# N64A_FA_E7x.net
KiCad netlist of a schematic drawn in EAGLE
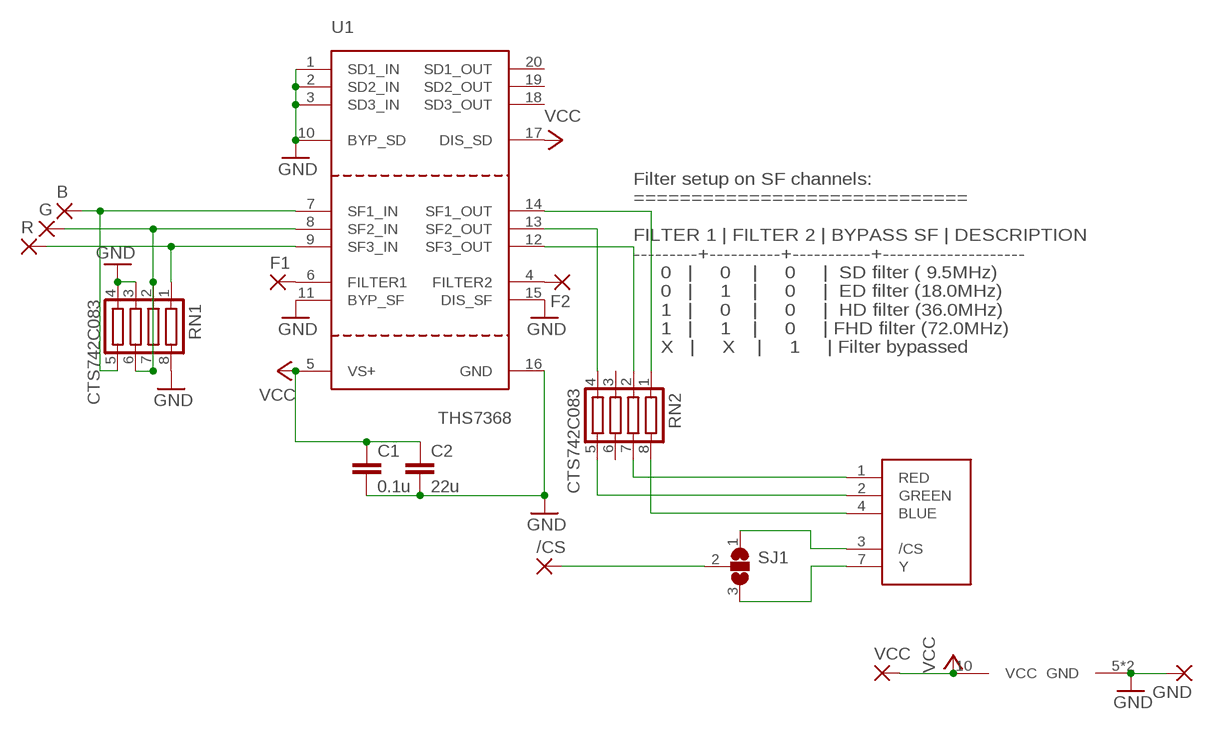
[diagram p0: schematic, sheet 1]

(export (version "E")
  (design (tool "Eeschema 10.0.6"))
  (components
    (comp (ref "/CS")
      (value "SMD2")
      (footprint "eagle-import:SMD1,27-2,54")
      (libsource (lib "eagle-import") (part "SMD2"))
    )
    (comp (ref "B")
      (value "SMD2")
      (footprint "eagle-import:SMD1,27-2,54")
      (libsource (lib "eagle-import") (part "SMD2"))
    )
    (comp (ref "C1")
      (value "0.1u")
      (footprint "eagle-import:C0603")
      (libsource (lib "eagle-import") (part "C-EUC0603"))
    )
    (comp (ref "C2")
      (value "22u")
      (footprint "eagle-import:C1206")
      (libsource (lib "eagle-import") (part "C-EUC1206"))
    )
    (comp (ref "F1")
      (value "SMD1")
      (footprint "eagle-import:SMD0,8-1,6")
      (libsource (lib "eagle-import") (part "SMD1"))
    )
    (comp (ref "F2")
      (value "SMD1")
      (footprint "eagle-import:SMD0,8-1,6")
      (libsource (lib "eagle-import") (part "SMD1"))
    )
    (comp (ref "G")
      (value "SMD2")
      (footprint "eagle-import:SMD1,27-2,54")
      (libsource (lib "eagle-import") (part "SMD2"))
    )
    (comp (ref "GND")
      (value "SMD2")
      (footprint "eagle-import:SMD1,27-2,54")
      (libsource (lib "eagle-import") (part "SMD2"))
    )
    (comp (ref "R")
      (value "SMD2")
      (footprint "eagle-import:SMD1,27-2,54")
      (libsource (lib "eagle-import") (part "SMD2"))
    )
    (comp (ref "RN1")
      (value "CTS742C083")
      (footprint "eagle-import:CTS742C083")
      (libsource (lib "eagle-import") (part "CTS742C083"))
    )
    (comp (ref "RN2")
      (value "CTS742C083")
      (footprint "eagle-import:CTS742C083")
      (libsource (lib "eagle-import") (part "CTS742C083"))
    )
    (comp (ref "SJ1")
      (value "SJ2W")
      (footprint "eagle-import:SJ_2")
      (libsource (lib "eagle-import") (part "SJ2W"))
    )
    (comp (ref "U$1")
      (value "SNES_MULTIAV_RGBSY")
      (footprint "eagle-import:SNES_MULTIAV_RGBSY")
      (libsource (lib "eagle-import") (part "SNES_MULTIAV_RGBSY"))
    )
    (comp (ref "U1")
      (value "THS7368")
      (footprint "eagle-import:THS7368")
      (libsource (lib "eagle-import") (part "THS7368"))
    )
    (comp (ref "VCC")
      (value "SMD2")
      (footprint "eagle-import:SMD1,27-2,54")
      (libsource (lib "eagle-import") (part "SMD2"))
    )
  )
  (nets
    (net (code "1") (name "GND") (class "Default")
      (node (ref "C1") (pin "2") (pinfunction "2_2") (pintype "passive"))
      (node (ref "C2") (pin "2") (pinfunction "2_2") (pintype "passive"))
      (node (ref "GND") (pin "1") (pinfunction "P_1") (pintype "passive"))
      (node (ref "RN1") (pin "3") (pinfunction "3_3") (pintype "passive"))
      (node (ref "RN1") (pin "4") (pinfunction "4_4") (pintype "passive"))
      (node (ref "RN1") (pin "8") (pinfunction "8_8") (pintype "passive"))
      (node (ref "U$1") (pin "5") (pinfunction "GND_5") (pintype "bidirectional"))
      (node (ref "U$1") (pin "6") (pinfunction "GND_6") (pintype "bidirectional"))
      (node (ref "U1") (pin "1") (pinfunction "SD1_IN_1") (pintype "input"))
      (node (ref "U1") (pin "10") (pinfunction "BYP_SD_10") (pintype "input"))
      (node (ref "U1") (pin "11") (pinfunction "BYP_SF_11") (pintype "input"))
      (node (ref "U1") (pin "15") (pinfunction "DIS_SF_15") (pintype "input"))
      (node (ref "U1") (pin "16") (pinfunction "GND_16") (pintype "power_in"))
      (node (ref "U1") (pin "2") (pinfunction "SD2_IN_2") (pintype "input"))
      (node (ref "U1") (pin "3") (pinfunction "SD3_IN_3") (pintype "input"))
    )
    (net (code "2") (name "Net-(/CS-P)") (class "Default")
      (node (ref "/CS") (pin "1") (pinfunction "P_1") (pintype "passive"))
      (node (ref "SJ1") (pin "2") (pinfunction "2_2") (pintype "passive"))
    )
    (net (code "3") (name "Net-(B-P)") (class "Default")
      (node (ref "B") (pin "1") (pinfunction "P_1") (pintype "passive"))
      (node (ref "RN1") (pin "5") (pinfunction "5_5") (pintype "passive"))
      (node (ref "U1") (pin "7") (pinfunction "SF1_IN_7") (pintype "input"))
    )
    (net (code "4") (name "Net-(F1-P)") (class "Default")
      (node (ref "F1") (pin "P$1") (pinfunction "P_P$1") (pintype "passive"))
      (node (ref "U1") (pin "6") (pinfunction "FILTER1_6") (pintype "input"))
    )
    (net (code "5") (name "Net-(F2-P)") (class "Default")
      (node (ref "F2") (pin "P$1") (pinfunction "P_P$1") (pintype "passive"))
      (node (ref "U1") (pin "4") (pinfunction "FILTER2_4") (pintype "input"))
    )
    (net (code "6") (name "Net-(G-P)") (class "Default")
      (node (ref "G") (pin "1") (pinfunction "P_1") (pintype "passive"))
      (node (ref "RN1") (pin "2") (pinfunction "2_2") (pintype "passive"))
      (node (ref "RN1") (pin "6") (pinfunction "6_6") (pintype "passive"))
      (node (ref "RN1") (pin "7") (pinfunction "7_7") (pintype "passive"))
      (node (ref "U1") (pin "8") (pinfunction "SF2_IN_8") (pintype "input"))
    )
    (net (code "7") (name "Net-(R-P)") (class "Default")
      (node (ref "R") (pin "1") (pinfunction "P_1") (pintype "passive"))
      (node (ref "RN1") (pin "1") (pinfunction "1_1") (pintype "passive"))
      (node (ref "U1") (pin "9") (pinfunction "SF3_IN_9") (pintype "input"))
    )
    (net (code "8") (name "Net-(U$1A-BLUE)") (class "Default")
      (node (ref "RN2") (pin "8") (pinfunction "8_8") (pintype "passive"))
      (node (ref "U$1") (pin "4") (pinfunction "BLUE_4") (pintype "bidirectional"))
    )
    (net (code "9") (name "Net-(U$1A-GREEN)") (class "Default")
      (node (ref "RN2") (pin "5") (pinfunction "5_5") (pintype "passive"))
      (node (ref "U$1") (pin "2") (pinfunction "GREEN_2") (pintype "bidirectional"))
    )
    (net (code "10") (name "Net-(U$1A-RED)") (class "Default")
      (node (ref "RN2") (pin "7") (pinfunction "7_7") (pintype "passive"))
      (node (ref "U$1") (pin "1") (pinfunction "RED_1") (pintype "bidirectional"))
    )
    (net (code "11") (name "Net-(U$1A-Y)") (class "Default")
      (node (ref "SJ1") (pin "3") (pinfunction "3_3") (pintype "passive"))
      (node (ref "U$1") (pin "7") (pinfunction "Y_7") (pintype "bidirectional"))
    )
    (net (code "12") (name "Net-(U$1A-{slash}CS)") (class "Default")
      (node (ref "SJ1") (pin "1") (pinfunction "1_1") (pintype "passive"))
      (node (ref "U$1") (pin "3") (pinfunction "/CS_3") (pintype "bidirectional"))
    )
    (net (code "13") (name "Net-(U1-SF1_OUT)") (class "Default")
      (node (ref "RN2") (pin "1") (pinfunction "1_1") (pintype "passive"))
      (node (ref "U1") (pin "14") (pinfunction "SF1_OUT_14") (pintype "output"))
    )
    (net (code "14") (name "Net-(U1-SF2_OUT)") (class "Default")
      (node (ref "RN2") (pin "4") (pinfunction "4_4") (pintype "passive"))
      (node (ref "U1") (pin "13") (pinfunction "SF2_OUT_13") (pintype "output"))
    )
    (net (code "15") (name "Net-(U1-SF3_OUT)") (class "Default")
      (node (ref "RN2") (pin "2") (pinfunction "2_2") (pintype "passive"))
      (node (ref "U1") (pin "12") (pinfunction "SF3_OUT_12") (pintype "output"))
    )
    (net (code "16") (name "VCC") (class "Default")
      (node (ref "C1") (pin "1") (pinfunction "1_1") (pintype "passive"))
      (node (ref "C2") (pin "1") (pinfunction "1_1") (pintype "passive"))
      (node (ref "U$1") (pin "10") (pinfunction "VCC_10") (pintype "bidirectional"))
      (node (ref "U1") (pin "17") (pinfunction "DIS_SD_17") (pintype "input"))
      (node (ref "U1") (pin "5") (pinfunction "VS+_5") (pintype "power_in"))
      (node (ref "VCC") (pin "1") (pinfunction "P_1") (pintype "passive"))
    )
    (net (code "17") (name "unconnected-(RN2-Pad3)") (class "Default")
      (node (ref "RN2") (pin "3") (pinfunction "3_3") (pintype "passive"))
    )
    (net (code "18") (name "unconnected-(RN2-Pad6)") (class "Default")
      (node (ref "RN2") (pin "6") (pinfunction "6_6") (pintype "passive"))
    )
    (net (code "19") (name "unconnected-(U1-SD1_OUT-Pad20)") (class "Default")
      (node (ref "U1") (pin "20") (pinfunction "SD1_OUT_20") (pintype "output"))
    )
    (net (code "20") (name "unconnected-(U1-SD2_OUT-Pad19)") (class "Default")
      (node (ref "U1") (pin "19") (pinfunction "SD2_OUT_19") (pintype "output"))
    )
    (net (code "21") (name "unconnected-(U1-SD3_OUT-Pad18)") (class "Default")
      (node (ref "U1") (pin "18") (pinfunction "SD3_OUT_18") (pintype "output"))
    )
  )
)
